# HEATER.net
KiCad netlist of a schematic drawn in Altium Designer
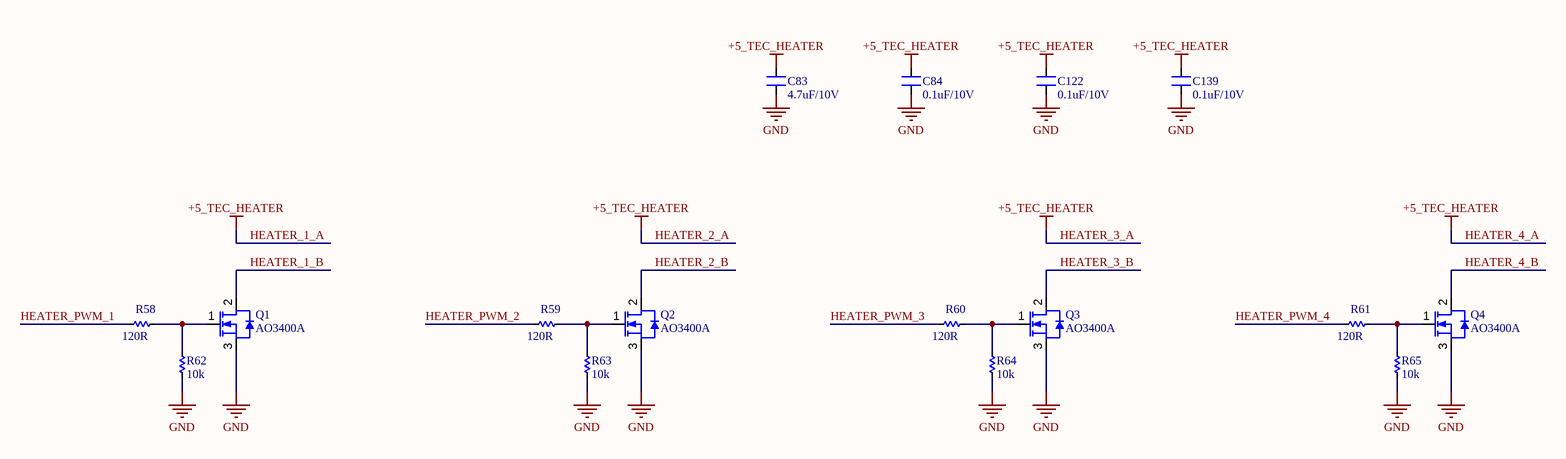
[diagram p0: HEATER.SchDoc]

(export (version "E")
  (design (tool "Eeschema 10.0.6"))
  (components
    (comp (ref "C83")
      (value "4.7uF/10V")
      (footprint "CAP_C_1608X80")
      (libsource (lib "Sang_library") (part "Capacitors"))
    )
    (comp (ref "C84")
      (value "0.1uF/10V")
      (footprint "CAP_C_1608X80")
      (libsource (lib "Sang_library") (part "Capacitors"))
    )
    (comp (ref "C122")
      (value "0.1uF/10V")
      (footprint "CAP_C_1608X80")
      (libsource (lib "Sang_library") (part "Capacitors"))
    )
    (comp (ref "C139")
      (value "0.1uF/10V")
      (footprint "CAP_C_1608X80")
      (libsource (lib "Sang_library") (part "Capacitors"))
    )
    (comp (ref "Q1")
      (value "AO3400A")
      (footprint "SOT23-13_2")
      (description "MOSFET N-CH 30V 5.7A SOT23-3L")
      (libsource (lib "Sang_library") (part "AO3400A"))
    )
    (comp (ref "Q2")
      (value "AO3400A")
      (footprint "SOT23-13_2")
      (description "MOSFET N-CH 30V 5.7A SOT23-3L")
      (libsource (lib "Sang_library") (part "AO3400A"))
    )
    (comp (ref "Q3")
      (value "AO3400A")
      (footprint "SOT23-13_2")
      (description "MOSFET N-CH 30V 5.7A SOT23-3L")
      (libsource (lib "Sang_library") (part "AO3400A"))
    )
    (comp (ref "Q4")
      (value "AO3400A")
      (footprint "SOT23-13_2")
      (description "MOSFET N-CH 30V 5.7A SOT23-3L")
      (libsource (lib "Sang_library") (part "AO3400A"))
    )
    (comp (ref "R58")
      (value "120R")
      (footprint "RES_C_1608X60")
      (description "SMD")
      (fields
        (field (name "MANUFACTURER") "Generic Components")
        (field (name "PUBLISHER") "Altium Hobart Technology Centre")
      )
      (libsource (lib "Sang_library") (part "Res SMD"))
    )
    (comp (ref "R59")
      (value "120R")
      (footprint "RES_C_1608X60")
      (description "SMD")
      (fields
        (field (name "MANUFACTURER") "Generic Components")
        (field (name "PUBLISHER") "Altium Hobart Technology Centre")
      )
      (libsource (lib "Sang_library") (part "Res SMD"))
    )
    (comp (ref "R60")
      (value "120R")
      (footprint "RES_C_1608X60")
      (description "SMD")
      (fields
        (field (name "MANUFACTURER") "Generic Components")
        (field (name "PUBLISHER") "Altium Hobart Technology Centre")
      )
      (libsource (lib "Sang_library") (part "Res SMD"))
    )
    (comp (ref "R61")
      (value "120R")
      (footprint "RES_C_1608X60")
      (description "SMD")
      (fields
        (field (name "MANUFACTURER") "Generic Components")
        (field (name "PUBLISHER") "Altium Hobart Technology Centre")
      )
      (libsource (lib "Sang_library") (part "Res SMD"))
    )
    (comp (ref "R62")
      (value "10k")
      (footprint "RES_C_1608X60")
      (description "SMD")
      (fields
        (field (name "MANUFACTURER") "Generic Components")
        (field (name "PUBLISHER") "Altium Hobart Technology Centre")
      )
      (libsource (lib "Sang_library") (part "Res SMD"))
    )
    (comp (ref "R63")
      (value "10k")
      (footprint "RES_C_1608X60")
      (description "SMD")
      (fields
        (field (name "MANUFACTURER") "Generic Components")
        (field (name "PUBLISHER") "Altium Hobart Technology Centre")
      )
      (libsource (lib "Sang_library") (part "Res SMD"))
    )
    (comp (ref "R64")
      (value "10k")
      (footprint "RES_C_1608X60")
      (description "SMD")
      (fields
        (field (name "MANUFACTURER") "Generic Components")
        (field (name "PUBLISHER") "Altium Hobart Technology Centre")
      )
      (libsource (lib "Sang_library") (part "Res SMD"))
    )
    (comp (ref "R65")
      (value "10k")
      (footprint "RES_C_1608X60")
      (description "SMD")
      (fields
        (field (name "MANUFACTURER") "Generic Components")
        (field (name "PUBLISHER") "Altium Hobart Technology Centre")
      )
      (libsource (lib "Sang_library") (part "Res SMD"))
    )
  )
  (nets
    (net (code "1") (name "+5_TEC_HEATER") (class "Default")
      (node (ref "C122") (pin "2") (pinfunction "2_2") (pintype "passive"))
      (node (ref "C139") (pin "2") (pinfunction "2_2") (pintype "passive"))
      (node (ref "C83") (pin "2") (pinfunction "2_2") (pintype "passive"))
      (node (ref "C84") (pin "2") (pinfunction "2_2") (pintype "passive"))
    )
    (net (code "2") (name "/HEATER_1_B") (class "Default")
      (node (ref "Q1") (pin "2") (pinfunction "D_2") (pintype "passive"))
    )
    (net (code "3") (name "/HEATER_2_B") (class "Default")
      (node (ref "Q2") (pin "2") (pinfunction "D_2") (pintype "passive"))
    )
    (net (code "4") (name "/HEATER_3_B") (class "Default")
      (node (ref "Q3") (pin "2") (pinfunction "D_2") (pintype "passive"))
    )
    (net (code "5") (name "/HEATER_4_B") (class "Default")
      (node (ref "Q4") (pin "2") (pinfunction "D_2") (pintype "passive"))
    )
    (net (code "6") (name "/HEATER_PWM_1") (class "Default")
      (node (ref "R58") (pin "1") (pinfunction "1_1") (pintype "passive"))
    )
    (net (code "7") (name "/HEATER_PWM_2") (class "Default")
      (node (ref "R59") (pin "1") (pinfunction "1_1") (pintype "passive"))
    )
    (net (code "8") (name "/HEATER_PWM_3") (class "Default")
      (node (ref "R60") (pin "1") (pinfunction "1_1") (pintype "passive"))
    )
    (net (code "9") (name "/HEATER_PWM_4") (class "Default")
      (node (ref "R61") (pin "1") (pinfunction "1_1") (pintype "passive"))
    )
    (net (code "10") (name "GND") (class "Default")
      (node (ref "C122") (pin "1") (pinfunction "1_1") (pintype "passive"))
      (node (ref "C139") (pin "1") (pinfunction "1_1") (pintype "passive"))
      (node (ref "C83") (pin "1") (pinfunction "1_1") (pintype "passive"))
      (node (ref "C84") (pin "1") (pinfunction "1_1") (pintype "passive"))
      (node (ref "Q1") (pin "3") (pinfunction "S_3") (pintype "passive"))
      (node (ref "Q2") (pin "3") (pinfunction "S_3") (pintype "passive"))
      (node (ref "Q3") (pin "3") (pinfunction "S_3") (pintype "passive"))
      (node (ref "Q4") (pin "3") (pinfunction "S_3") (pintype "passive"))
      (node (ref "R62") (pin "1") (pinfunction "1_1") (pintype "passive"))
      (node (ref "R63") (pin "1") (pinfunction "1_1") (pintype "passive"))
      (node (ref "R64") (pin "1") (pinfunction "1_1") (pintype "passive"))
      (node (ref "R65") (pin "1") (pinfunction "1_1") (pintype "passive"))
    )
    (net (code "11") (name "Net-(Q1-G)") (class "Default")
      (node (ref "Q1") (pin "1") (pinfunction "G_1") (pintype "passive"))
      (node (ref "R58") (pin "2") (pinfunction "2_2") (pintype "passive"))
      (node (ref "R62") (pin "2") (pinfunction "2_2") (pintype "passive"))
    )
    (net (code "12") (name "Net-(Q2-G)") (class "Default")
      (node (ref "Q2") (pin "1") (pinfunction "G_1") (pintype "passive"))
      (node (ref "R59") (pin "2") (pinfunction "2_2") (pintype "passive"))
      (node (ref "R63") (pin "2") (pinfunction "2_2") (pintype "passive"))
    )
    (net (code "13") (name "Net-(Q3-G)") (class "Default")
      (node (ref "Q3") (pin "1") (pinfunction "G_1") (pintype "passive"))
      (node (ref "R60") (pin "2") (pinfunction "2_2") (pintype "passive"))
      (node (ref "R64") (pin "2") (pinfunction "2_2") (pintype "passive"))
    )
    (net (code "14") (name "Net-(Q4-G)") (class "Default")
      (node (ref "Q4") (pin "1") (pinfunction "G_1") (pintype "passive"))
      (node (ref "R61") (pin "2") (pinfunction "2_2") (pintype "passive"))
      (node (ref "R65") (pin "2") (pinfunction "2_2") (pintype "passive"))
    )
  )
)
